# arduino_uno_to_attiny_x313.net
KiCad netlist of a schematic drawn in EAGLE
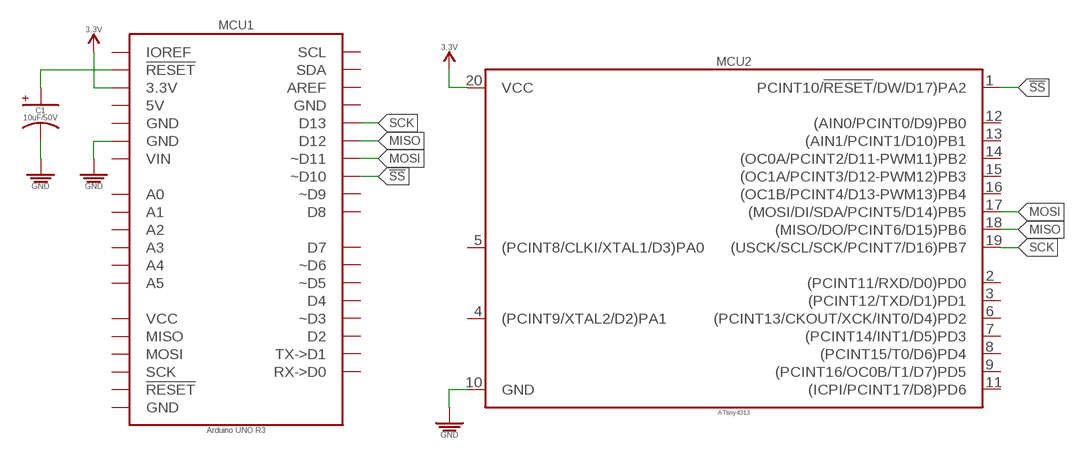
[diagram p0: schematic, sheet 1]

(export (version "E")
  (design (tool "Eeschema 10.0.6"))
  (components
    (comp (ref "C1")
      (value "10uF/50V")
      (footprint "eagle-import:_AE_PTH-DIA5-LS2-H5")
      (fields (field (name "MFR") "Panasonic Electronic Components") (field (name "MPN") "ECE-A1HKA100"))
      (libsource (lib "eagle-import") (part "10UF-POLARIZED_PTH_50V-20%"))
    )
    (comp (ref "MCU1")
      (value "Arduino UNO R3")
      (footprint "eagle-import:ARDUINO_UNO_R3")
      (fields (field (name "MFR") "Arduino") (field (name "MPN") "A000066"))
      (libsource (lib "eagle-import") (part "ARDUINO_UNO_R3"))
    )
    (comp (ref "MCU2")
      (value "ATtiny4313")
      (footprint "eagle-import:DIP793W45P254L2573H533Q20B_DIP-20_ATTINY-X313")
      (fields (field (name "MFR") "Microchip Technology") (field (name "MPN") "ATTINY4313-PU"))
      (libsource (lib "eagle-import") (part "ATTINY-X313_DIP-20_ATTINY-4313"))
    )
  )
  (nets
    (net (code "1") (name "/~{SS}") (class "Default")
      (node (ref "MCU1") (pin "D10") (pinfunction "~{D10}_D10") (pintype "bidirectional"))
      (node (ref "MCU2") (pin "1") (pinfunction "PCINT10/~{RESET}/DW/D17)PA2_1") (pintype "bidirectional"))
    )
    (net (code "2") (name "3.3V") (class "Default")
      (node (ref "MCU1") (pin "3.3V") (pinfunction "3.3V_3.3V") (pintype "bidirectional"))
      (node (ref "MCU2") (pin "20") (pinfunction "VCC_20") (pintype "passive"))
    )
    (net (code "3") (name "GND") (class "Default")
      (node (ref "C1") (pin "-") (pinfunction "K_-") (pintype "passive"))
      (node (ref "MCU1") (pin "GND@3") (pinfunction "GND_GND@3") (pintype "bidirectional"))
      (node (ref "MCU2") (pin "10") (pinfunction "GND_10") (pintype "passive"))
    )
    (net (code "4") (name "MISO") (class "Default")
      (node (ref "MCU1") (pin "D12") (pinfunction "D12_D12") (pintype "bidirectional"))
      (node (ref "MCU2") (pin "18") (pinfunction "(MISO/DO/PCINT6/D15)PB6_18") (pintype "bidirectional"))
    )
    (net (code "5") (name "MOSI") (class "Default")
      (node (ref "MCU1") (pin "D11") (pinfunction "~{D11}_D11") (pintype "bidirectional"))
      (node (ref "MCU2") (pin "17") (pinfunction "(MOSI/DI/SDA/PCINT5/D14)PB5_17") (pintype "bidirectional"))
    )
    (net (code "6") (name "Net-(C1-A)") (class "Default")
      (node (ref "C1") (pin "+") (pinfunction "A_+") (pintype "passive"))
      (node (ref "MCU1") (pin "RESET@1") (pinfunction "~{RESET}_RESET@1") (pintype "bidirectional"))
    )
    (net (code "7") (name "SCK") (class "Default")
      (node (ref "MCU1") (pin "D13") (pinfunction "D13_D13") (pintype "bidirectional"))
      (node (ref "MCU2") (pin "19") (pinfunction "(USCK/SCL/SCK/PCINT7/D16)PB7_19") (pintype "bidirectional"))
    )
    (net (code "8") (name "unconnected-(MCU1-GND-PadGND@1)") (class "Default")
      (node (ref "MCU1") (pin "GND@1") (pinfunction "GND_GND@1") (pintype "bidirectional"))
    )
    (net (code "9") (name "unconnected-(MCU1-GND-PadGND@2)") (class "Default")
      (node (ref "MCU1") (pin "GND@2") (pinfunction "GND_GND@2") (pintype "bidirectional"))
    )
    (net (code "10") (name "unconnected-(MCU1-GND-PadGND@4)") (class "Default")
      (node (ref "MCU1") (pin "GND@4") (pinfunction "GND_GND@4") (pintype "bidirectional"))
    )
    (net (code "11") (name "unconnected-(MCU1-Pad5V)") (class "Default")
      (node (ref "MCU1") (pin "5V") (pinfunction "5V_5V") (pintype "bidirectional"))
    )
    (net (code "12") (name "unconnected-(MCU1-PadA0)") (class "Default")
      (node (ref "MCU1") (pin "A0") (pinfunction "A0_A0") (pintype "bidirectional"))
    )
    (net (code "13") (name "unconnected-(MCU1-PadA1)") (class "Default")
      (node (ref "MCU1") (pin "A1") (pinfunction "A1_A1") (pintype "bidirectional"))
    )
    (net (code "14") (name "unconnected-(MCU1-PadA2)") (class "Default")
      (node (ref "MCU1") (pin "A2") (pinfunction "A2_A2") (pintype "bidirectional"))
    )
    (net (code "15") (name "unconnected-(MCU1-PadA3)") (class "Default")
      (node (ref "MCU1") (pin "A3") (pinfunction "A3_A3") (pintype "bidirectional"))
    )
    (net (code "16") (name "unconnected-(MCU1-PadA4)") (class "Default")
      (node (ref "MCU1") (pin "A4") (pinfunction "A4_A4") (pintype "bidirectional"))
    )
    (net (code "17") (name "unconnected-(MCU1-PadA5)") (class "Default")
      (node (ref "MCU1") (pin "A5") (pinfunction "A5_A5") (pintype "bidirectional"))
    )
    (net (code "18") (name "unconnected-(MCU1-PadAREF)") (class "Default")
      (node (ref "MCU1") (pin "AREF") (pinfunction "AREF_AREF") (pintype "bidirectional"))
    )
    (net (code "19") (name "unconnected-(MCU1-PadD2)") (class "Default")
      (node (ref "MCU1") (pin "D2") (pinfunction "D2_D2") (pintype "bidirectional"))
    )
    (net (code "20") (name "unconnected-(MCU1-PadD4)") (class "Default")
      (node (ref "MCU1") (pin "D4") (pinfunction "D4_D4") (pintype "bidirectional"))
    )
    (net (code "21") (name "unconnected-(MCU1-PadD7)") (class "Default")
      (node (ref "MCU1") (pin "D7") (pinfunction "D7_D7") (pintype "bidirectional"))
    )
    (net (code "22") (name "unconnected-(MCU1-PadD8)") (class "Default")
      (node (ref "MCU1") (pin "D8") (pinfunction "D8_D8") (pintype "bidirectional"))
    )
    (net (code "23") (name "unconnected-(MCU1-PadIOREF)") (class "Default")
      (node (ref "MCU1") (pin "IOREF") (pinfunction "IOREF_IOREF") (pintype "bidirectional"))
    )
    (net (code "24") (name "unconnected-(MCU1-PadMISO)") (class "Default")
      (node (ref "MCU1") (pin "MISO") (pinfunction "MISO_MISO") (pintype "bidirectional"))
    )
    (net (code "25") (name "unconnected-(MCU1-PadMOSI)") (class "Default")
      (node (ref "MCU1") (pin "MOSI") (pinfunction "MOSI_MOSI") (pintype "bidirectional"))
    )
    (net (code "26") (name "unconnected-(MCU1-PadSCK)") (class "Default")
      (node (ref "MCU1") (pin "SCK") (pinfunction "SCK_SCK") (pintype "bidirectional"))
    )
    (net (code "27") (name "unconnected-(MCU1-PadSCL)") (class "Default")
      (node (ref "MCU1") (pin "SCL") (pinfunction "SCL_SCL") (pintype "bidirectional"))
    )
    (net (code "28") (name "unconnected-(MCU1-PadSDA)") (class "Default")
      (node (ref "MCU1") (pin "SDA") (pinfunction "SDA_SDA") (pintype "bidirectional"))
    )
    (net (code "29") (name "unconnected-(MCU1-PadVCC)") (class "Default")
      (node (ref "MCU1") (pin "VCC") (pinfunction "VCC_VCC") (pintype "bidirectional"))
    )
    (net (code "30") (name "unconnected-(MCU1-PadVIN)") (class "Default")
      (node (ref "MCU1") (pin "VIN") (pinfunction "VIN_VIN") (pintype "bidirectional"))
    )
    (net (code "31") (name "unconnected-(MCU1-RX->D0-PadD0)") (class "Default")
      (node (ref "MCU1") (pin "D0") (pinfunction "RX->D0_D0") (pintype "bidirectional"))
    )
    (net (code "32") (name "unconnected-(MCU1-TX->D1-PadD1)") (class "Default")
      (node (ref "MCU1") (pin "D1") (pinfunction "TX->D1_D1") (pintype "bidirectional"))
    )
    (net (code "33") (name "unconnected-(MCU1-~{D3}-PadD3)") (class "Default")
      (node (ref "MCU1") (pin "D3") (pinfunction "~{D3}_D3") (pintype "bidirectional"))
    )
    (net (code "34") (name "unconnected-(MCU1-~{D5}-PadD5)") (class "Default")
      (node (ref "MCU1") (pin "D5") (pinfunction "~{D5}_D5") (pintype "bidirectional"))
    )
    (net (code "35") (name "unconnected-(MCU1-~{D6}-PadD6)") (class "Default")
      (node (ref "MCU1") (pin "D6") (pinfunction "~{D6}_D6") (pintype "bidirectional"))
    )
    (net (code "36") (name "unconnected-(MCU1-~{D9}-PadD9)") (class "Default")
      (node (ref "MCU1") (pin "D9") (pinfunction "~{D9}_D9") (pintype "bidirectional"))
    )
    (net (code "37") (name "unconnected-(MCU1-~{RESET}-PadRESET@2)") (class "Default")
      (node (ref "MCU1") (pin "RESET@2") (pinfunction "~{RESET}_RESET@2") (pintype "bidirectional"))
    )
    (net (code "38") (name "unconnected-(MCU2-(AIN0{slash}PCINT0{slash}D9)PB0-Pad12)") (class "Default")
      (node (ref "MCU2") (pin "12") (pinfunction "(AIN0/PCINT0/D9)PB0_12") (pintype "bidirectional"))
    )
    (net (code "39") (name "unconnected-(MCU2-(AIN1{slash}PCINT1{slash}D10)PB1-Pad13)") (class "Default")
      (node (ref "MCU2") (pin "13") (pinfunction "(AIN1/PCINT1/D10)PB1_13") (pintype "bidirectional"))
    )
    (net (code "40") (name "unconnected-(MCU2-(ICPI{slash}PCINT17{slash}D8)PD6-Pad11)") (class "Default")
      (node (ref "MCU2") (pin "11") (pinfunction "(ICPI/PCINT17/D8)PD6_11") (pintype "bidirectional"))
    )
    (net (code "41") (name "unconnected-(MCU2-(OC0A{slash}PCINT2{slash}D11-PWM11)PB2-Pad14)") (class "Default")
      (node (ref "MCU2") (pin "14") (pinfunction "(OC0A/PCINT2/D11-PWM11)PB2_14") (pintype "bidirectional"))
    )
    (net (code "42") (name "unconnected-(MCU2-(OC1A{slash}PCINT3{slash}D12-PWM12)PB3-Pad15)") (class "Default")
      (node (ref "MCU2") (pin "15") (pinfunction "(OC1A/PCINT3/D12-PWM12)PB3_15") (pintype "bidirectional"))
    )
    (net (code "43") (name "unconnected-(MCU2-(OC1B{slash}PCINT4{slash}D13-PWM13)PB4-Pad16)") (class "Default")
      (node (ref "MCU2") (pin "16") (pinfunction "(OC1B/PCINT4/D13-PWM13)PB4_16") (pintype "bidirectional"))
    )
    (net (code "44") (name "unconnected-(MCU2-(PCINT8{slash}CLKI{slash}XTAL1{slash}D3)PA0-Pad5)") (class "Default")
      (node (ref "MCU2") (pin "5") (pinfunction "(PCINT8/CLKI/XTAL1/D3)PA0_5") (pintype "bidirectional"))
    )
    (net (code "45") (name "unconnected-(MCU2-(PCINT9{slash}XTAL2{slash}D2)PA1-Pad4)") (class "Default")
      (node (ref "MCU2") (pin "4") (pinfunction "(PCINT9/XTAL2/D2)PA1_4") (pintype "bidirectional"))
    )
    (net (code "46") (name "unconnected-(MCU2-(PCINT11{slash}RXD{slash}D0)PD0-Pad2)") (class "Default")
      (node (ref "MCU2") (pin "2") (pinfunction "(PCINT11/RXD/D0)PD0_2") (pintype "bidirectional"))
    )
    (net (code "47") (name "unconnected-(MCU2-(PCINT12{slash}TXD{slash}D1)PD1-Pad3)") (class "Default")
      (node (ref "MCU2") (pin "3") (pinfunction "(PCINT12/TXD/D1)PD1_3") (pintype "bidirectional"))
    )
    (net (code "48") (name "unconnected-(MCU2-(PCINT13{slash}CKOUT{slash}XCK{slash}INT0{slash}D4)PD2-Pad6)") (class "Default")
      (node (ref "MCU2") (pin "6") (pinfunction "(PCINT13/CKOUT/XCK/INT0/D4)PD2_6") (pintype "bidirectional"))
    )
    (net (code "49") (name "unconnected-(MCU2-(PCINT14{slash}INT1{slash}D5)PD3-Pad7)") (class "Default")
      (node (ref "MCU2") (pin "7") (pinfunction "(PCINT14/INT1/D5)PD3_7") (pintype "bidirectional"))
    )
    (net (code "50") (name "unconnected-(MCU2-(PCINT15{slash}T0{slash}D6)PD4-Pad8)") (class "Default")
      (node (ref "MCU2") (pin "8") (pinfunction "(PCINT15/T0/D6)PD4_8") (pintype "bidirectional"))
    )
    (net (code "51") (name "unconnected-(MCU2-(PCINT16{slash}OC0B{slash}T1{slash}D7)PD5-Pad9)") (class "Default")
      (node (ref "MCU2") (pin "9") (pinfunction "(PCINT16/OC0B/T1/D7)PD5_9") (pintype "bidirectional"))
    )
  )
)
